# newUA_6.net
KiCad netlist of a schematic drawn in Altium Designer
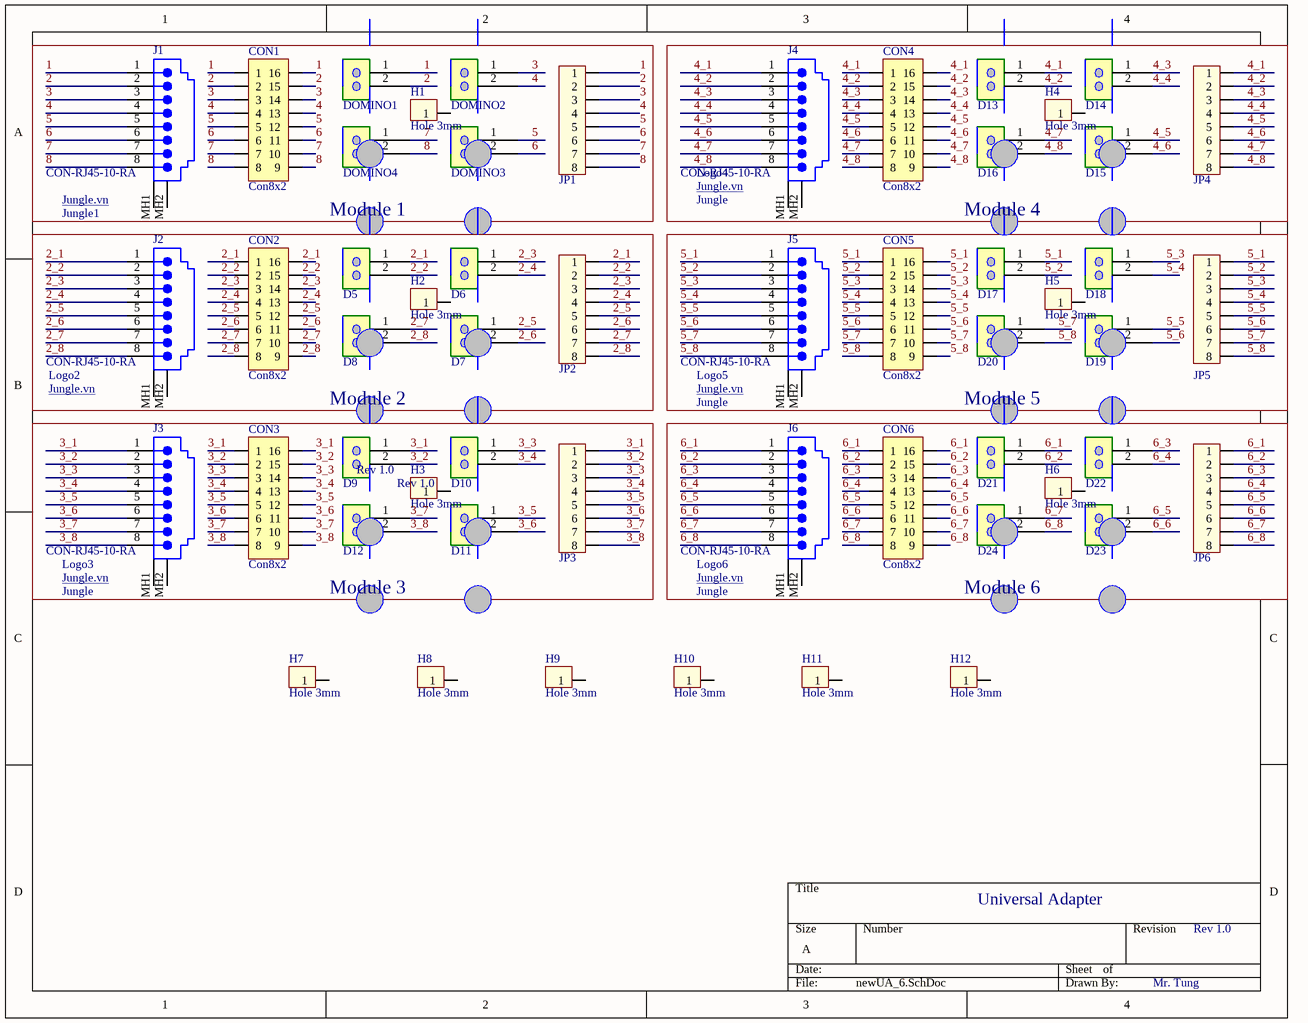
[diagram p0: newUA_6.SchDoc]

(export (version "E")
  (design (tool "Eeschema 10.0.6"))
  (components
    (comp (ref "CON1") (value "Con8x2") (footprint "HEAD8x2") (libsource (lib "Thach") (part "Con8x2")))
    (comp (ref "CON2") (value "Con8x2") (footprint "HEAD8x2") (libsource (lib "Thach") (part "Con8x2")))
    (comp (ref "CON3") (value "Con8x2") (footprint "HEAD8x2") (libsource (lib "Thach") (part "Con8x2")))
    (comp (ref "CON4") (value "Con8x2") (footprint "HEAD8x2") (libsource (lib "Thach") (part "Con8x2")))
    (comp (ref "CON5") (value "Con8x2") (footprint "HEAD8x2") (libsource (lib "Thach") (part "Con8x2")))
    (comp (ref "CON6") (value "Con8x2") (footprint "HEAD8x2") (libsource (lib "Thach") (part "Con8x2")))
    (comp (ref "D1")
      (value "DOMINO1")
      (footprint "Domino2_small")
      (libsource (lib "Thach") (part "Domino 2"))
    )
    (comp (ref "D2")
      (value "DOMINO2")
      (footprint "Domino2_small")
      (libsource (lib "Thach") (part "Domino 2"))
    )
    (comp (ref "D3")
      (value "DOMINO3")
      (footprint "Domino2_small")
      (libsource (lib "Thach") (part "Domino 2"))
    )
    (comp (ref "D4")
      (value "DOMINO4")
      (footprint "Domino2_small")
      (libsource (lib "Thach") (part "Domino 2"))
    )
    (comp (ref "D5") (value "D5") (footprint "Domino2_small") (libsource (lib "Thach") (part "Domino 2")))
    (comp (ref "D6") (value "D6") (footprint "Domino2_small") (libsource (lib "Thach") (part "Domino 2")))
    (comp (ref "D7") (value "D7") (footprint "Domino2_small") (libsource (lib "Thach") (part "Domino 2")))
    (comp (ref "D8") (value "D8") (footprint "Domino2_small") (libsource (lib "Thach") (part "Domino 2")))
    (comp (ref "D9") (value "D9") (footprint "Domino2_small") (libsource (lib "Thach") (part "Domino 2")))
    (comp (ref "D10") (value "D10") (footprint "Domino2_small") (libsource (lib "Thach") (part "Domino 2")))
    (comp (ref "D11") (value "D11") (footprint "Domino2_small") (libsource (lib "Thach") (part "Domino 2")))
    (comp (ref "D12") (value "D12") (footprint "Domino2_small") (libsource (lib "Thach") (part "Domino 2")))
    (comp (ref "D13") (value "D13") (footprint "Domino2_small") (libsource (lib "Thach") (part "Domino 2")))
    (comp (ref "D14") (value "D14") (footprint "Domino2_small") (libsource (lib "Thach") (part "Domino 2")))
    (comp (ref "D15") (value "D15") (footprint "Domino2_small") (libsource (lib "Thach") (part "Domino 2")))
    (comp (ref "D16") (value "D16") (footprint "Domino2_small") (libsource (lib "Thach") (part "Domino 2")))
    (comp (ref "D17") (value "D17") (footprint "Domino2_small") (libsource (lib "Thach") (part "Domino 2")))
    (comp (ref "D18") (value "D18") (footprint "Domino2_small") (libsource (lib "Thach") (part "Domino 2")))
    (comp (ref "D19") (value "D19") (footprint "Domino2_small") (libsource (lib "Thach") (part "Domino 2")))
    (comp (ref "D20") (value "D20") (footprint "Domino2_small") (libsource (lib "Thach") (part "Domino 2")))
    (comp (ref "D21") (value "D21") (footprint "Domino2_small") (libsource (lib "Thach") (part "Domino 2")))
    (comp (ref "D22") (value "D22") (footprint "Domino2_small") (libsource (lib "Thach") (part "Domino 2")))
    (comp (ref "D23") (value "D23") (footprint "Domino2_small") (libsource (lib "Thach") (part "Domino 2")))
    (comp (ref "D24") (value "D24") (footprint "Domino2_small") (libsource (lib "Thach") (part "Domino 2")))
    (comp (ref "H1") (value "Hole 3mm") (footprint "Hole_3mm") (libsource (lib "Thach") (part "Hole_3mm")))
    (comp (ref "H2") (value "Hole 3mm") (footprint "Hole_3mm") (libsource (lib "Thach") (part "Hole_3mm")))
    (comp (ref "H3") (value "Hole 3mm") (footprint "Hole_3mm") (libsource (lib "Thach") (part "Hole_3mm")))
    (comp (ref "H4") (value "Hole 3mm") (footprint "Hole_3mm") (libsource (lib "Thach") (part "Hole_3mm")))
    (comp (ref "H5") (value "Hole 3mm") (footprint "Hole_3mm") (libsource (lib "Thach") (part "Hole_3mm")))
    (comp (ref "H6") (value "Hole 3mm") (footprint "Hole_3mm") (libsource (lib "Thach") (part "Hole_3mm")))
    (comp (ref "H7") (value "Hole 3mm") (footprint "Hole_3mm") (libsource (lib "Thach") (part "Hole_3mm")))
    (comp (ref "H8") (value "Hole 3mm") (footprint "Hole_3mm") (libsource (lib "Thach") (part "Hole_3mm")))
    (comp (ref "H9") (value "Hole 3mm") (footprint "Hole_3mm") (libsource (lib "Thach") (part "Hole_3mm")))
    (comp (ref "H10") (value "Hole 3mm") (footprint "Hole_3mm") (libsource (lib "Thach") (part "Hole_3mm")))
    (comp (ref "H11") (value "Hole 3mm") (footprint "Hole_3mm") (libsource (lib "Thach") (part "Hole_3mm")))
    (comp (ref "H12") (value "Hole 3mm") (footprint "Hole_3mm") (libsource (lib "Thach") (part "Hole_3mm")))
    (comp (ref "J1")
      (value "CON-RJ45-10-RA")
      (footprint "RJ45_tme")
      (description "Right Angle, Standard Profile, External Shield PCB Jack")
      (libsource (lib "Thach") (part "CON-RJ45-10-RA"))
    )
    (comp (ref "J2")
      (value "CON-RJ45-10-RA")
      (footprint "RJ45_tme")
      (description "Right Angle, Standard Profile, External Shield PCB Jack")
      (libsource (lib "Thach") (part "CON-RJ45-10-RA"))
    )
    (comp (ref "J3")
      (value "CON-RJ45-10-RA")
      (footprint "RJ45_tme")
      (description "Right Angle, Standard Profile, External Shield PCB Jack")
      (libsource (lib "Thach") (part "CON-RJ45-10-RA"))
    )
    (comp (ref "J4")
      (value "CON-RJ45-10-RA")
      (footprint "RJ45_tme")
      (description "Right Angle, Standard Profile, External Shield PCB Jack")
      (libsource (lib "Thach") (part "CON-RJ45-10-RA"))
    )
    (comp (ref "J5")
      (value "CON-RJ45-10-RA")
      (footprint "RJ45_tme")
      (description "Right Angle, Standard Profile, External Shield PCB Jack")
      (libsource (lib "Thach") (part "CON-RJ45-10-RA"))
    )
    (comp (ref "J6")
      (value "CON-RJ45-10-RA")
      (footprint "RJ45_tme")
      (description "Right Angle, Standard Profile, External Shield PCB Jack")
      (libsource (lib "Thach") (part "CON-RJ45-10-RA"))
    )
    (comp (ref "JP1")
      (value "JP8")
      (footprint "CON8mod")
      (description "Connector 8")
      (libsource (lib "Thach") (part "Con8"))
    )
    (comp (ref "JP2")
      (value "JP8")
      (footprint "CON8mod")
      (description "Connector 8")
      (libsource (lib "Thach") (part "Con8"))
    )
    (comp (ref "JP3")
      (value "JP8")
      (footprint "CON8mod")
      (description "Connector 8")
      (libsource (lib "Thach") (part "Con8"))
    )
    (comp (ref "JP4")
      (value "JP8")
      (footprint "CON8mod")
      (description "Connector 8")
      (libsource (lib "Thach") (part "Con8"))
    )
    (comp (ref "JP5")
      (value "JP8")
      (footprint "CON8mod")
      (description "Connector 8")
      (libsource (lib "Thach") (part "Con8"))
    )
    (comp (ref "JP6")
      (value "JP8")
      (footprint "CON8mod")
      (description "Connector 8")
      (libsource (lib "Thach") (part "Con8"))
    )
    (comp (ref "Logo1") (value "Jungle1") (footprint "Jungle") (libsource (lib "logo") (part "Jungle")))
    (comp (ref "Logo2") (value "Jungle2") (footprint "Jungle") (libsource (lib "logo") (part "Jungle")))
    (comp (ref "Logo3") (value "Jungle") (footprint "Jungle") (libsource (lib "logo") (part "Jungle")))
    (comp (ref "Logo4") (value "Jungle") (footprint "Jungle") (libsource (lib "logo") (part "Jungle")))
    (comp (ref "Logo5") (value "Jungle") (footprint "Jungle") (libsource (lib "logo") (part "Jungle")))
    (comp (ref "Logo6") (value "Jungle") (footprint "Jungle") (libsource (lib "logo") (part "Jungle")))
  )
  (nets
    (net (code "1") (name "/1") (class "Default")
      (node (ref "CON1") (pin "1") (pinfunction "1_1") (pintype "passive"))
      (node (ref "CON1") (pin "16") (pinfunction "16_16") (pintype "passive"))
      (node (ref "D1") (pin "1") (pintype "passive"))
      (node (ref "J1") (pin "1") (pinfunction "1_1") (pintype "passive"))
      (node (ref "JP1") (pin "1") (pinfunction "1_1") (pintype "passive"))
    )
    (net (code "2") (name "/2") (class "Default")
      (node (ref "CON1") (pin "15") (pinfunction "15_15") (pintype "passive"))
      (node (ref "CON1") (pin "2") (pinfunction "2_2") (pintype "passive"))
      (node (ref "D1") (pin "2") (pintype "passive"))
      (node (ref "J1") (pin "2") (pinfunction "2_2") (pintype "passive"))
      (node (ref "JP1") (pin "2") (pinfunction "2_2") (pintype "passive"))
    )
    (net (code "3") (name "/2_1") (class "Default")
      (node (ref "CON2") (pin "1") (pinfunction "1_1") (pintype "passive"))
      (node (ref "CON2") (pin "16") (pinfunction "16_16") (pintype "passive"))
      (node (ref "D5") (pin "1") (pintype "passive"))
      (node (ref "J2") (pin "1") (pinfunction "1_1") (pintype "passive"))
      (node (ref "JP2") (pin "1") (pinfunction "1_1") (pintype "passive"))
    )
    (net (code "4") (name "/2_2") (class "Default")
      (node (ref "CON2") (pin "15") (pinfunction "15_15") (pintype "passive"))
      (node (ref "CON2") (pin "2") (pinfunction "2_2") (pintype "passive"))
      (node (ref "D5") (pin "2") (pintype "passive"))
      (node (ref "J2") (pin "2") (pinfunction "2_2") (pintype "passive"))
      (node (ref "JP2") (pin "2") (pinfunction "2_2") (pintype "passive"))
    )
    (net (code "5") (name "/2_3") (class "Default")
      (node (ref "CON2") (pin "14") (pinfunction "14_14") (pintype "passive"))
      (node (ref "CON2") (pin "3") (pinfunction "3_3") (pintype "passive"))
      (node (ref "D6") (pin "1") (pintype "passive"))
      (node (ref "J2") (pin "3") (pinfunction "3_3") (pintype "passive"))
      (node (ref "JP2") (pin "3") (pinfunction "3_3") (pintype "passive"))
    )
    (net (code "6") (name "/2_4") (class "Default")
      (node (ref "CON2") (pin "13") (pinfunction "13_13") (pintype "passive"))
      (node (ref "CON2") (pin "4") (pinfunction "4_4") (pintype "passive"))
      (node (ref "D6") (pin "2") (pintype "passive"))
      (node (ref "J2") (pin "4") (pinfunction "4_4") (pintype "passive"))
      (node (ref "JP2") (pin "4") (pinfunction "4_4") (pintype "passive"))
    )
    (net (code "7") (name "/2_5") (class "Default")
      (node (ref "CON2") (pin "12") (pinfunction "12_12") (pintype "passive"))
      (node (ref "CON2") (pin "5") (pinfunction "5_5") (pintype "passive"))
      (node (ref "D7") (pin "1") (pintype "passive"))
      (node (ref "J2") (pin "5") (pinfunction "5_5") (pintype "passive"))
      (node (ref "JP2") (pin "5") (pinfunction "5_5") (pintype "passive"))
    )
    (net (code "8") (name "/2_6") (class "Default")
      (node (ref "CON2") (pin "11") (pinfunction "11_11") (pintype "passive"))
      (node (ref "CON2") (pin "6") (pinfunction "6_6") (pintype "passive"))
      (node (ref "D7") (pin "2") (pintype "passive"))
      (node (ref "J2") (pin "6") (pinfunction "6_6") (pintype "passive"))
      (node (ref "JP2") (pin "6") (pinfunction "6_6") (pintype "passive"))
    )
    (net (code "9") (name "/2_7") (class "Default")
      (node (ref "CON2") (pin "10") (pinfunction "10_10") (pintype "passive"))
      (node (ref "CON2") (pin "7") (pinfunction "7_7") (pintype "passive"))
      (node (ref "D8") (pin "1") (pintype "passive"))
      (node (ref "J2") (pin "7") (pinfunction "7_7") (pintype "passive"))
      (node (ref "JP2") (pin "7") (pinfunction "7_7") (pintype "passive"))
    )
    (net (code "10") (name "/2_8") (class "Default")
      (node (ref "CON2") (pin "8") (pinfunction "8_8") (pintype "passive"))
      (node (ref "CON2") (pin "9") (pinfunction "9_9") (pintype "passive"))
      (node (ref "D8") (pin "2") (pintype "passive"))
      (node (ref "J2") (pin "8") (pinfunction "8_8") (pintype "passive"))
      (node (ref "JP2") (pin "8") (pinfunction "8_8") (pintype "passive"))
    )
    (net (code "11") (name "/3") (class "Default")
      (node (ref "CON1") (pin "14") (pinfunction "14_14") (pintype "passive"))
      (node (ref "CON1") (pin "3") (pinfunction "3_3") (pintype "passive"))
      (node (ref "D2") (pin "1") (pintype "passive"))
      (node (ref "J1") (pin "3") (pinfunction "3_3") (pintype "passive"))
      (node (ref "JP1") (pin "3") (pinfunction "3_3") (pintype "passive"))
    )
    (net (code "12") (name "/3_1") (class "Default")
      (node (ref "CON3") (pin "1") (pinfunction "1_1") (pintype "passive"))
      (node (ref "CON3") (pin "16") (pinfunction "16_16") (pintype "passive"))
      (node (ref "D9") (pin "1") (pintype "passive"))
      (node (ref "J3") (pin "1") (pinfunction "1_1") (pintype "passive"))
      (node (ref "JP3") (pin "1") (pinfunction "1_1") (pintype "passive"))
    )
    (net (code "13") (name "/3_2") (class "Default")
      (node (ref "CON3") (pin "15") (pinfunction "15_15") (pintype "passive"))
      (node (ref "CON3") (pin "2") (pinfunction "2_2") (pintype "passive"))
      (node (ref "D9") (pin "2") (pintype "passive"))
      (node (ref "J3") (pin "2") (pinfunction "2_2") (pintype "passive"))
      (node (ref "JP3") (pin "2") (pinfunction "2_2") (pintype "passive"))
    )
    (net (code "14") (name "/3_3") (class "Default")
      (node (ref "CON3") (pin "14") (pinfunction "14_14") (pintype "passive"))
      (node (ref "CON3") (pin "3") (pinfunction "3_3") (pintype "passive"))
      (node (ref "D10") (pin "1") (pintype "passive"))
      (node (ref "J3") (pin "3") (pinfunction "3_3") (pintype "passive"))
      (node (ref "JP3") (pin "3") (pinfunction "3_3") (pintype "passive"))
    )
    (net (code "15") (name "/3_4") (class "Default")
      (node (ref "CON3") (pin "13") (pinfunction "13_13") (pintype "passive"))
      (node (ref "CON3") (pin "4") (pinfunction "4_4") (pintype "passive"))
      (node (ref "D10") (pin "2") (pintype "passive"))
      (node (ref "J3") (pin "4") (pinfunction "4_4") (pintype "passive"))
      (node (ref "JP3") (pin "4") (pinfunction "4_4") (pintype "passive"))
    )
    (net (code "16") (name "/3_5") (class "Default")
      (node (ref "CON3") (pin "12") (pinfunction "12_12") (pintype "passive"))
      (node (ref "CON3") (pin "5") (pinfunction "5_5") (pintype "passive"))
      (node (ref "D11") (pin "1") (pintype "passive"))
      (node (ref "J3") (pin "5") (pinfunction "5_5") (pintype "passive"))
      (node (ref "JP3") (pin "5") (pinfunction "5_5") (pintype "passive"))
    )
    (net (code "17") (name "/3_6") (class "Default")
      (node (ref "CON3") (pin "11") (pinfunction "11_11") (pintype "passive"))
      (node (ref "CON3") (pin "6") (pinfunction "6_6") (pintype "passive"))
      (node (ref "D11") (pin "2") (pintype "passive"))
      (node (ref "J3") (pin "6") (pinfunction "6_6") (pintype "passive"))
      (node (ref "JP3") (pin "6") (pinfunction "6_6") (pintype "passive"))
    )
    (net (code "18") (name "/3_7") (class "Default")
      (node (ref "CON3") (pin "10") (pinfunction "10_10") (pintype "passive"))
      (node (ref "CON3") (pin "7") (pinfunction "7_7") (pintype "passive"))
      (node (ref "D12") (pin "1") (pintype "passive"))
      (node (ref "J3") (pin "7") (pinfunction "7_7") (pintype "passive"))
      (node (ref "JP3") (pin "7") (pinfunction "7_7") (pintype "passive"))
    )
    (net (code "19") (name "/3_8") (class "Default")
      (node (ref "CON3") (pin "8") (pinfunction "8_8") (pintype "passive"))
      (node (ref "CON3") (pin "9") (pinfunction "9_9") (pintype "passive"))
      (node (ref "D12") (pin "2") (pintype "passive"))
      (node (ref "J3") (pin "8") (pinfunction "8_8") (pintype "passive"))
      (node (ref "JP3") (pin "8") (pinfunction "8_8") (pintype "passive"))
    )
    (net (code "20") (name "/4") (class "Default")
      (node (ref "CON1") (pin "13") (pinfunction "13_13") (pintype "passive"))
      (node (ref "CON1") (pin "4") (pinfunction "4_4") (pintype "passive"))
      (node (ref "D2") (pin "2") (pintype "passive"))
      (node (ref "J1") (pin "4") (pinfunction "4_4") (pintype "passive"))
      (node (ref "JP1") (pin "4") (pinfunction "4_4") (pintype "passive"))
    )
    (net (code "21") (name "/4_1") (class "Default")
      (node (ref "CON4") (pin "1") (pinfunction "1_1") (pintype "passive"))
      (node (ref "CON4") (pin "16") (pinfunction "16_16") (pintype "passive"))
      (node (ref "D13") (pin "1") (pintype "passive"))
      (node (ref "J4") (pin "1") (pinfunction "1_1") (pintype "passive"))
      (node (ref "JP4") (pin "1") (pinfunction "1_1") (pintype "passive"))
    )
    (net (code "22") (name "/4_2") (class "Default")
      (node (ref "CON4") (pin "15") (pinfunction "15_15") (pintype "passive"))
      (node (ref "CON4") (pin "2") (pinfunction "2_2") (pintype "passive"))
      (node (ref "D13") (pin "2") (pintype "passive"))
      (node (ref "J4") (pin "2") (pinfunction "2_2") (pintype "passive"))
      (node (ref "JP4") (pin "2") (pinfunction "2_2") (pintype "passive"))
    )
    (net (code "23") (name "/4_3") (class "Default")
      (node (ref "CON4") (pin "14") (pinfunction "14_14") (pintype "passive"))
      (node (ref "CON4") (pin "3") (pinfunction "3_3") (pintype "passive"))
      (node (ref "D14") (pin "1") (pintype "passive"))
      (node (ref "J4") (pin "3") (pinfunction "3_3") (pintype "passive"))
      (node (ref "JP4") (pin "3") (pinfunction "3_3") (pintype "passive"))
    )
    (net (code "24") (name "/4_4") (class "Default")
      (node (ref "CON4") (pin "13") (pinfunction "13_13") (pintype "passive"))
      (node (ref "CON4") (pin "4") (pinfunction "4_4") (pintype "passive"))
      (node (ref "D14") (pin "2") (pintype "passive"))
      (node (ref "J4") (pin "4") (pinfunction "4_4") (pintype "passive"))
      (node (ref "JP4") (pin "4") (pinfunction "4_4") (pintype "passive"))
    )
    (net (code "25") (name "/4_5") (class "Default")
      (node (ref "CON4") (pin "12") (pinfunction "12_12") (pintype "passive"))
      (node (ref "CON4") (pin "5") (pinfunction "5_5") (pintype "passive"))
      (node (ref "D15") (pin "1") (pintype "passive"))
      (node (ref "J4") (pin "5") (pinfunction "5_5") (pintype "passive"))
      (node (ref "JP4") (pin "5") (pinfunction "5_5") (pintype "passive"))
    )
    (net (code "26") (name "/4_6") (class "Default")
      (node (ref "CON4") (pin "11") (pinfunction "11_11") (pintype "passive"))
      (node (ref "CON4") (pin "6") (pinfunction "6_6") (pintype "passive"))
      (node (ref "D15") (pin "2") (pintype "passive"))
      (node (ref "J4") (pin "6") (pinfunction "6_6") (pintype "passive"))
      (node (ref "JP4") (pin "6") (pinfunction "6_6") (pintype "passive"))
    )
    (net (code "27") (name "/4_7") (class "Default")
      (node (ref "CON4") (pin "10") (pinfunction "10_10") (pintype "passive"))
      (node (ref "CON4") (pin "7") (pinfunction "7_7") (pintype "passive"))
      (node (ref "D16") (pin "1") (pintype "passive"))
      (node (ref "J4") (pin "7") (pinfunction "7_7") (pintype "passive"))
      (node (ref "JP4") (pin "7") (pinfunction "7_7") (pintype "passive"))
    )
    (net (code "28") (name "/4_8") (class "Default")
      (node (ref "CON4") (pin "8") (pinfunction "8_8") (pintype "passive"))
      (node (ref "CON4") (pin "9") (pinfunction "9_9") (pintype "passive"))
      (node (ref "D16") (pin "2") (pintype "passive"))
      (node (ref "J4") (pin "8") (pinfunction "8_8") (pintype "passive"))
      (node (ref "JP4") (pin "8") (pinfunction "8_8") (pintype "passive"))
    )
    (net (code "29") (name "/5") (class "Default")
      (node (ref "CON1") (pin "12") (pinfunction "12_12") (pintype "passive"))
      (node (ref "CON1") (pin "5") (pinfunction "5_5") (pintype "passive"))
      (node (ref "D3") (pin "1") (pintype "passive"))
      (node (ref "J1") (pin "5") (pinfunction "5_5") (pintype "passive"))
      (node (ref "JP1") (pin "5") (pinfunction "5_5") (pintype "passive"))
    )
    (net (code "30") (name "/5_1") (class "Default")
      (node (ref "CON5") (pin "1") (pinfunction "1_1") (pintype "passive"))
      (node (ref "CON5") (pin "16") (pinfunction "16_16") (pintype "passive"))
      (node (ref "D17") (pin "1") (pintype "passive"))
      (node (ref "J5") (pin "1") (pinfunction "1_1") (pintype "passive"))
      (node (ref "JP5") (pin "1") (pinfunction "1_1") (pintype "passive"))
    )
    (net (code "31") (name "/5_2") (class "Default")
      (node (ref "CON5") (pin "15") (pinfunction "15_15") (pintype "passive"))
      (node (ref "CON5") (pin "2") (pinfunction "2_2") (pintype "passive"))
      (node (ref "D17") (pin "2") (pintype "passive"))
      (node (ref "J5") (pin "2") (pinfunction "2_2") (pintype "passive"))
      (node (ref "JP5") (pin "2") (pinfunction "2_2") (pintype "passive"))
    )
    (net (code "32") (name "/5_3") (class "Default")
      (node (ref "CON5") (pin "14") (pinfunction "14_14") (pintype "passive"))
      (node (ref "CON5") (pin "3") (pinfunction "3_3") (pintype "passive"))
      (node (ref "D18") (pin "1") (pintype "passive"))
      (node (ref "J5") (pin "3") (pinfunction "3_3") (pintype "passive"))
      (node (ref "JP5") (pin "3") (pinfunction "3_3") (pintype "passive"))
    )
    (net (code "33") (name "/5_4") (class "Default")
      (node (ref "CON5") (pin "13") (pinfunction "13_13") (pintype "passive"))
      (node (ref "CON5") (pin "4") (pinfunction "4_4") (pintype "passive"))
      (node (ref "D18") (pin "2") (pintype "passive"))
      (node (ref "J5") (pin "4") (pinfunction "4_4") (pintype "passive"))
      (node (ref "JP5") (pin "4") (pinfunction "4_4") (pintype "passive"))
    )
    (net (code "34") (name "/5_5") (class "Default")
      (node (ref "CON5") (pin "12") (pinfunction "12_12") (pintype "passive"))
      (node (ref "CON5") (pin "5") (pinfunction "5_5") (pintype "passive"))
      (node (ref "D19") (pin "1") (pintype "passive"))
      (node (ref "J5") (pin "5") (pinfunction "5_5") (pintype "passive"))
      (node (ref "JP5") (pin "5") (pinfunction "5_5") (pintype "passive"))
    )
    (net (code "35") (name "/5_6") (class "Default")
      (node (ref "CON5") (pin "11") (pinfunction "11_11") (pintype "passive"))
      (node (ref "CON5") (pin "6") (pinfunction "6_6") (pintype "passive"))
      (node (ref "D19") (pin "2") (pintype "passive"))
      (node (ref "J5") (pin "6") (pinfunction "6_6") (pintype "passive"))
      (node (ref "JP5") (pin "6") (pinfunction "6_6") (pintype "passive"))
    )
    (net (code "36") (name "/5_7") (class "Default")
      (node (ref "CON5") (pin "10") (pinfunction "10_10") (pintype "passive"))
      (node (ref "CON5") (pin "7") (pinfunction "7_7") (pintype "passive"))
      (node (ref "D20") (pin "1") (pintype "passive"))
      (node (ref "J5") (pin "7") (pinfunction "7_7") (pintype "passive"))
      (node (ref "JP5") (pin "7") (pinfunction "7_7") (pintype "passive"))
    )
    (net (code "37") (name "/5_8") (class "Default")
      (node (ref "CON5") (pin "8") (pinfunction "8_8") (pintype "passive"))
      (node (ref "CON5") (pin "9") (pinfunction "9_9") (pintype "passive"))
      (node (ref "D20") (pin "2") (pintype "passive"))
      (node (ref "J5") (pin "8") (pinfunction "8_8") (pintype "passive"))
      (node (ref "JP5") (pin "8") (pinfunction "8_8") (pintype "passive"))
    )
    (net (code "38") (name "/6") (class "Default")
      (node (ref "CON1") (pin "11") (pinfunction "11_11") (pintype "passive"))
      (node (ref "CON1") (pin "6") (pinfunction "6_6") (pintype "passive"))
      (node (ref "D3") (pin "2") (pintype "passive"))
      (node (ref "J1") (pin "6") (pinfunction "6_6") (pintype "passive"))
      (node (ref "JP1") (pin "6") (pinfunction "6_6") (pintype "passive"))
    )
    (net (code "39") (name "/6_1") (class "Default")
      (node (ref "CON6") (pin "1") (pinfunction "1_1") (pintype "passive"))
      (node (ref "CON6") (pin "16") (pinfunction "16_16") (pintype "passive"))
      (node (ref "D21") (pin "1") (pintype "passive"))
      (node (ref "J6") (pin "1") (pinfunction "1_1") (pintype "passive"))
      (node (ref "JP6") (pin "1") (pinfunction "1_1") (pintype "passive"))
    )
    (net (code "40") (name "/6_2") (class "Default")
      (node (ref "CON6") (pin "15") (pinfunction "15_15") (pintype "passive"))
      (node (ref "CON6") (pin "2") (pinfunction "2_2") (pintype "passive"))
      (node (ref "D21") (pin "2") (pintype "passive"))
      (node (ref "J6") (pin "2") (pinfunction "2_2") (pintype "passive"))
      (node (ref "JP6") (pin "2") (pinfunction "2_2") (pintype "passive"))
    )
    (net (code "41") (name "/6_3") (class "Default")
      (node (ref "CON6") (pin "14") (pinfunction "14_14") (pintype "passive"))
      (node (ref "CON6") (pin "3") (pinfunction "3_3") (pintype "passive"))
      (node (ref "D22") (pin "1") (pintype "passive"))
      (node (ref "J6") (pin "3") (pinfunction "3_3") (pintype "passive"))
      (node (ref "JP6") (pin "3") (pinfunction "3_3") (pintype "passive"))
    )
    (net (code "42") (name "/6_4") (class "Default")
      (node (ref "CON6") (pin "13") (pinfunction "13_13") (pintype "passive"))
      (node (ref "CON6") (pin "4") (pinfunction "4_4") (pintype "passive"))
      (node (ref "D22") (pin "2") (pintype "passive"))
      (node (ref "J6") (pin "4") (pinfunction "4_4") (pintype "passive"))
      (node (ref "JP6") (pin "4") (pinfunction "4_4") (pintype "passive"))
    )
    (net (code "43") (name "/6_5") (class "Default")
      (node (ref "CON6") (pin "12") (pinfunction "12_12") (pintype "passive"))
      (node (ref "CON6") (pin "5") (pinfunction "5_5") (pintype "passive"))
      (node (ref "D23") (pin "1") (pintype "passive"))
      (node (ref "J6") (pin "5") (pinfunction "5_5") (pintype "passive"))
      (node (ref "JP6") (pin "5") (pinfunction "5_5") (pintype "passive"))
    )
    (net (code "44") (name "/6_6") (class "Default")
      (node (ref "CON6") (pin "11") (pinfunction "11_11") (pintype "passive"))
      (node (ref "CON6") (pin "6") (pinfunction "6_6") (pintype "passive"))
      (node (ref "D23") (pin "2") (pintype "passive"))
      (node (ref "J6") (pin "6") (pinfunction "6_6") (pintype "passive"))
      (node (ref "JP6") (pin "6") (pinfunction "6_6") (pintype "passive"))
    )
    (net (code "45") (name "/6_7") (class "Default")
      (node (ref "CON6") (pin "10") (pinfunction "10_10") (pintype "passive"))
      (node (ref "CON6") (pin "7") (pinfunction "7_7") (pintype "passive"))
      (node (ref "D24") (pin "1") (pintype "passive"))
      (node (ref "J6") (pin "7") (pinfunction "7_7") (pintype "passive"))
      (node (ref "JP6") (pin "7") (pinfunction "7_7") (pintype "passive"))
    )
    (net (code "46") (name "/6_8") (class "Default")
      (node (ref "CON6") (pin "8") (pinfunction "8_8") (pintype "passive"))
      (node (ref "CON6") (pin "9") (pinfunction "9_9") (pintype "passive"))
      (node (ref "D24") (pin "2") (pintype "passive"))
      (node (ref "J6") (pin "8") (pinfunction "8_8") (pintype "passive"))
      (node (ref "JP6") (pin "8") (pinfunction "8_8") (pintype "passive"))
    )
    (net (code "47") (name "/7") (class "Default")
      (node (ref "CON1") (pin "10") (pinfunction "10_10") (pintype "passive"))
      (node (ref "CON1") (pin "7") (pinfunction "7_7") (pintype "passive"))
      (node (ref "D4") (pin "1") (pintype "passive"))
      (node (ref "J1") (pin "7") (pinfunction "7_7") (pintype "passive"))
      (node (ref "JP1") (pin "7") (pinfunction "7_7") (pintype "passive"))
    )
    (net (code "48") (name "/8") (class "Default")
      (node (ref "CON1") (pin "8") (pinfunction "8_8") (pintype "passive"))
      (node (ref "CON1") (pin "9") (pinfunction "9_9") (pintype "passive"))
      (node (ref "D4") (pin "2") (pintype "passive"))
      (node (ref "J1") (pin "8") (pinfunction "8_8") (pintype "passive"))
      (node (ref "JP1") (pin "8") (pinfunction "8_8") (pintype "passive"))
    )
    (net (code "49") (name "unconnected-(H1-Pad1)") (class "Default")
      (node (ref "H1") (pin "1") (pinfunction "1_1") (pintype "passive"))
    )
    (net (code "50") (name "unconnected-(H2-Pad1)") (class "Default")
      (node (ref "H2") (pin "1") (pinfunction "1_1") (pintype "passive"))
    )
    (net (code "51") (name "unconnected-(H3-Pad1)") (class "Default")
      (node (ref "H3") (pin "1") (pinfunction "1_1") (pintype "passive"))
    )
    (net (code "52") (name "unconnected-(H4-Pad1)") (class "Default")
      (node (ref "H4") (pin "1") (pinfunction "1_1") (pintype "passive"))
    )
    (net (code "53") (name "unconnected-(H5-Pad1)") (class "Default")
      (node (ref "H5") (pin "1") (pinfunction "1_1") (pintype "passive"))
    )
    (net (code "54") (name "unconnected-(H6-Pad1)") (class "Default")
      (node (ref "H6") (pin "1") (pinfunction "1_1") (pintype "passive"))
    )
    (net (code "55") (name "unconnected-(H7-Pad1)") (class "Default")
      (node (ref "H7") (pin "1") (pinfunction "1_1") (pintype "passive"))
    )
    (net (code "56") (name "unconnected-(H8-Pad1)") (class "Default")
      (node (ref "H8") (pin "1") (pinfunction "1_1") (pintype "passive"))
    )
    (net (code "57") (name "unconnected-(H9-Pad1)") (class "Default")
      (node (ref "H9") (pin "1") (pinfunction "1_1") (pintype "passive"))
    )
    (net (code "58") (name "unconnected-(H10-Pad1)") (class "Default")
      (node (ref "H10") (pin "1") (pinfunction "1_1") (pintype "passive"))
    )
    (net (code "59") (name "unconnected-(H11-Pad1)") (class "Default")
      (node (ref "H11") (pin "1") (pinfunction "1_1") (pintype "passive"))
    )
    (net (code "60") (name "unconnected-(H12-Pad1)") (class "Default")
      (node (ref "H12") (pin "1") (pinfunction "1_1") (pintype "passive"))
    )
    (net (code "61") (name "unconnected-(J1-Shield-PadMH1)") (class "Default")
      (node (ref "J1") (pin "MH1") (pinfunction "Shield_MH1") (pintype "passive"))
    )
    (net (code "62") (name "unconnected-(J1-Shield-PadMH2)") (class "Default")
      (node (ref "J1") (pin "MH2") (pinfunction "Shield_MH2") (pintype "passive"))
    )
    (net (code "63") (name "unconnected-(J2-Shield-PadMH1)") (class "Default")
      (node (ref "J2") (pin "MH1") (pinfunction "Shield_MH1") (pintype "passive"))
    )
    (net (code "64") (name "unconnected-(J2-Shield-PadMH2)") (class "Default")
      (node (ref "J2") (pin "MH2") (pinfunction "Shield_MH2") (pintype "passive"))
    )
    (net (code "65") (name "unconnected-(J3-Shield-PadMH1)") (class "Default")
      (node (ref "J3") (pin "MH1") (pinfunction "Shield_MH1") (pintype "passive"))
    )
    (net (code "66") (name "unconnected-(J3-Shield-PadMH2)") (class "Default")
      (node (ref "J3") (pin "MH2") (pinfunction "Shield_MH2") (pintype "passive"))
    )
    (net (code "67") (name "unconnected-(J4-Shield-PadMH1)") (class "Default")
      (node (ref "J4") (pin "MH1") (pinfunction "Shield_MH1") (pintype "passive"))
    )
    (net (code "68") (name "unconnected-(J4-Shield-PadMH2)") (class "Default")
      (node (ref "J4") (pin "MH2") (pinfunction "Shield_MH2") (pintype "passive"))
    )
    (net (code "69") (name "unconnected-(J5-Shield-PadMH1)") (class "Default")
      (node (ref "J5") (pin "MH1") (pinfunction "Shield_MH1") (pintype "passive"))
    )
    (net (code "70") (name "unconnected-(J5-Shield-PadMH2)") (class "Default")
      (node (ref "J5") (pin "MH2") (pinfunction "Shield_MH2") (pintype "passive"))
    )
    (net (code "71") (name "unconnected-(J6-Shield-PadMH1)") (class "Default")
      (node (ref "J6") (pin "MH1") (pinfunction "Shield_MH1") (pintype "passive"))
    )
    (net (code "72") (name "unconnected-(J6-Shield-PadMH2)") (class "Default")
      (node (ref "J6") (pin "MH2") (pinfunction "Shield_MH2") (pintype "passive"))
    )
  )
)
